# MCU.net
KiCad netlist of a schematic drawn in Altium Designer
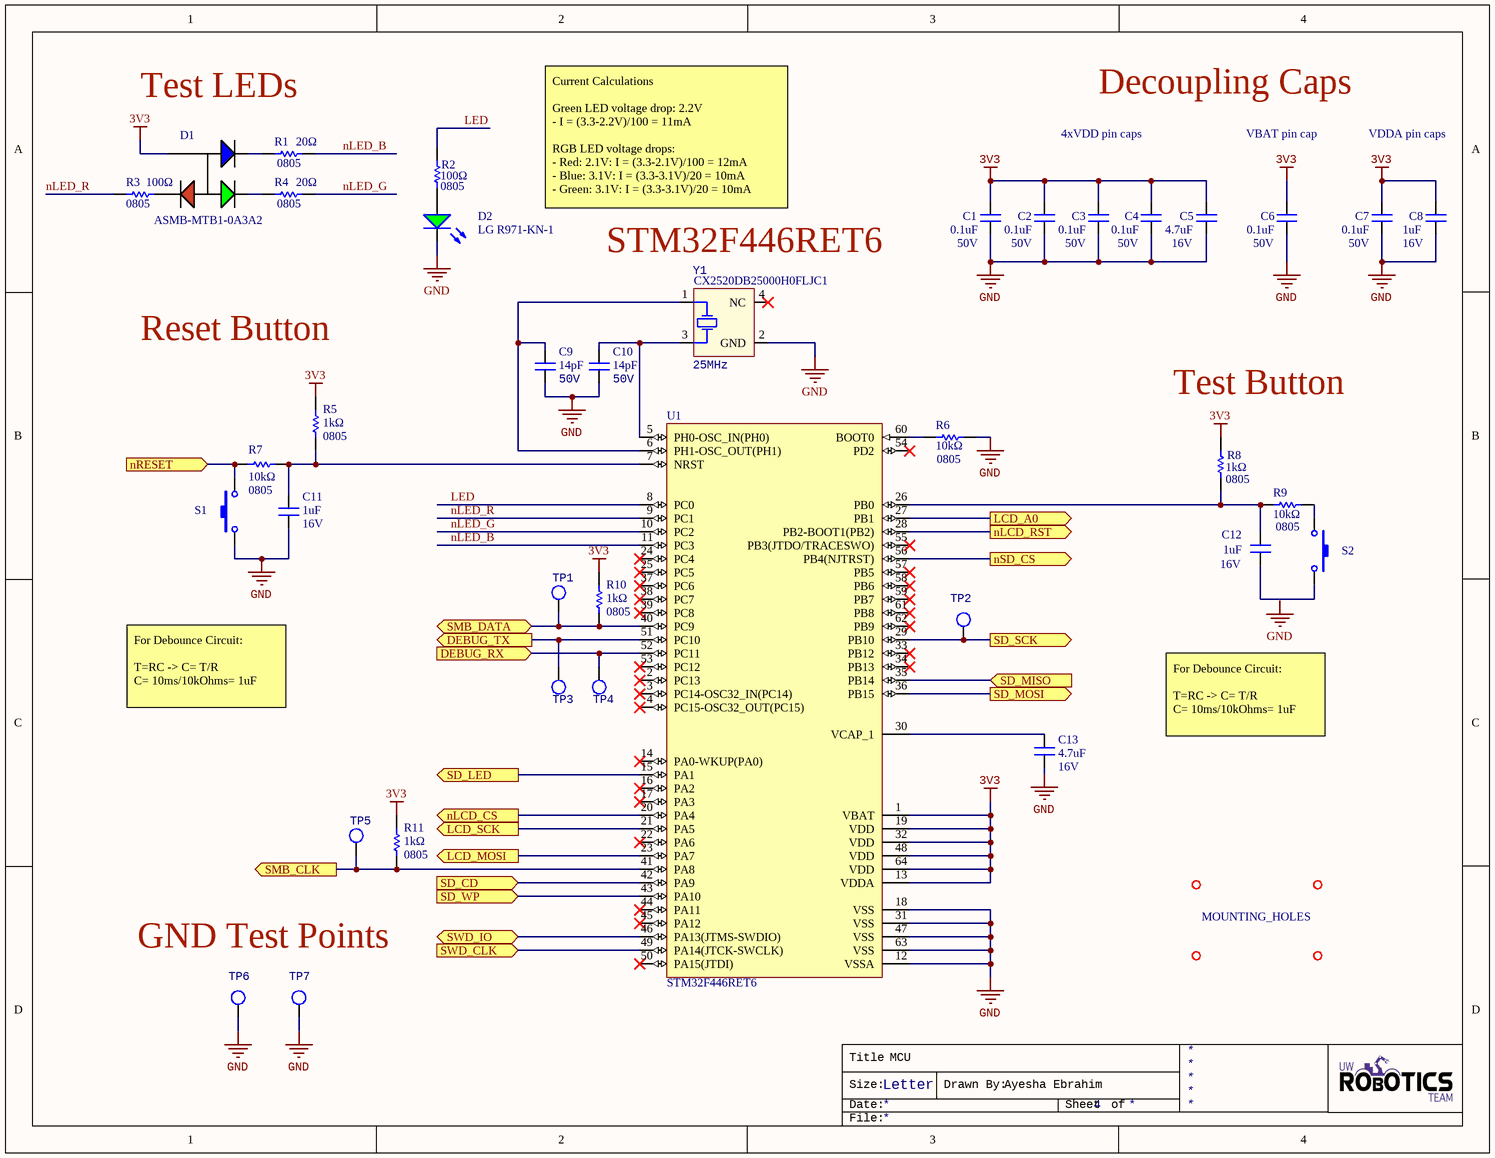
[diagram p0: MCU.SchDoc]

(export (version "E")
  (design (tool "Eeschema 10.0.6"))
  (components
    (comp (ref "C1")
      (value "0.1uF")
      (footprint "CAPC2012X140N")
      (description "CAP CER 0.1UF 50V X7R 0805")
      (fields
        (field (name "TOLERANCE") "10%")
        (field (name "VOLTAGE RATING") "50V")
        (field (name "Comment") "CAP_0.1uF_50V_0805")
      )
      (libsource (lib "UWRT_Schematic_Library_2020") (part "CAP_0.1uF_50V_0805"))
    )
    (comp (ref "C2")
      (value "0.1uF")
      (footprint "CAPC2012X140N")
      (description "CAP CER 0.1UF 50V X7R 0805")
      (fields
        (field (name "TOLERANCE") "10%")
        (field (name "VOLTAGE RATING") "50V")
        (field (name "Comment") "CAP_0.1uF_50V_0805")
      )
      (libsource (lib "UWRT_Schematic_Library_2020") (part "CAP_0.1uF_50V_0805"))
    )
    (comp (ref "C3")
      (value "0.1uF")
      (footprint "CAPC2012X140N")
      (description "CAP CER 0.1UF 50V X7R 0805")
      (fields
        (field (name "TOLERANCE") "10%")
        (field (name "VOLTAGE RATING") "50V")
        (field (name "Comment") "CAP_0.1uF_50V_0805")
      )
      (libsource (lib "UWRT_Schematic_Library_2020") (part "CAP_0.1uF_50V_0805"))
    )
    (comp (ref "C4")
      (value "0.1uF")
      (footprint "CAPC2012X140N")
      (description "CAP CER 0.1UF 50V X7R 0805")
      (fields
        (field (name "TOLERANCE") "10%")
        (field (name "VOLTAGE RATING") "50V")
        (field (name "Comment") "CAP_0.1uF_50V_0805")
      )
      (libsource (lib "UWRT_Schematic_Library_2020") (part "CAP_0.1uF_50V_0805"))
    )
    (comp (ref "C5")
      (value "4.7uF")
      (footprint "CAPC2012X140N")
      (description "CAP CER 4.7UF 16V X5R 0805")
      (fields
        (field (name "TOLERANCE") "10%")
        (field (name "VOLTAGE RATING") "16V")
        (field (name "Comment") "CAP_4.7uF_16V_0805")
      )
      (libsource (lib "UWRT_Schematic_Library_2020") (part "CAP_4.7uF_16V_0805"))
    )
    (comp (ref "C6")
      (value "0.1uF")
      (footprint "CAPC2012X140N")
      (description "CAP CER 0.1UF 50V X7R 0805")
      (fields
        (field (name "TOLERANCE") "10%")
        (field (name "VOLTAGE RATING") "50V")
        (field (name "Comment") "CAP_0.1uF_50V_0805")
      )
      (libsource (lib "UWRT_Schematic_Library_2020") (part "CAP_0.1uF_50V_0805"))
    )
    (comp (ref "C7")
      (value "0.1uF")
      (footprint "CAPC2012X140N")
      (description "CAP CER 0.1UF 50V X7R 0805")
      (fields
        (field (name "TOLERANCE") "10%")
        (field (name "VOLTAGE RATING") "50V")
        (field (name "Comment") "CAP_0.1uF_50V_0805")
      )
      (libsource (lib "UWRT_Schematic_Library_2020") (part "CAP_0.1uF_50V_0805"))
    )
    (comp (ref "C8")
      (value "1uF")
      (footprint "CAPC2012X140N")
      (description "CAP CER 1UF 16V X7R 0805")
      (fields
        (field (name "TOLERANCE") "10%")
        (field (name "VOLTAGE RATING") "16V")
        (field (name "Comment") "CAP_1uF_16V_0805")
      )
      (libsource (lib "UWRT_Schematic_Library_2020") (part "CAP_1uF_16V_0805"))
    )
    (comp (ref "C9")
      (value "14pF")
      (footprint "CAPC0603(1608)55_N")
      (description "Cap Ceramic 14pF 50V C0G 5% SMD 0603 125C Cardboard T/R")
      (fields
        (field (name "TOLERANCE") "5%")
        (field (name "VOLTAGE RATING (DC)") "50V")
        (field (name "Comment") "CL10C140JB8NNNC")
      )
      (libsource (lib "UWRT_Schematic_Library_2020") (part "CL10C140JB8NNNC"))
    )
    (comp (ref "C10")
      (value "14pF")
      (footprint "CAPC0603(1608)55_N")
      (description "Cap Ceramic 14pF 50V C0G 5% SMD 0603 125C Cardboard T/R")
      (fields
        (field (name "TOLERANCE") "5%")
        (field (name "VOLTAGE RATING (DC)") "50V")
        (field (name "Comment") "CL10C140JB8NNNC")
      )
      (libsource (lib "UWRT_Schematic_Library_2020") (part "CL10C140JB8NNNC"))
    )
    (comp (ref "C11")
      (value "1uF")
      (footprint "CAPC2012X140N")
      (description "CAP CER 1UF 16V X7R 0805")
      (fields
        (field (name "TOLERANCE") "10%")
        (field (name "VOLTAGE RATING") "16V")
        (field (name "Comment") "CAP_1uF_16V_0805")
      )
      (libsource (lib "UWRT_Schematic_Library_2020") (part "CAP_1uF_16V_0805"))
    )
    (comp (ref "C12")
      (value "1uF")
      (footprint "CAPC2012X140N")
      (description "CAP CER 1UF 16V X7R 0805")
      (fields
        (field (name "TOLERANCE") "10%")
        (field (name "VOLTAGE RATING") "16V")
        (field (name "Comment") "CAP_1uF_16V_0805")
      )
      (libsource (lib "UWRT_Schematic_Library_2020") (part "CAP_1uF_16V_0805"))
    )
    (comp (ref "C13")
      (value "4.7uF")
      (footprint "CAPC2012X140N")
      (description "CAP CER 4.7UF 16V X5R 0805")
      (fields
        (field (name "TOLERANCE") "10%")
        (field (name "VOLTAGE RATING") "16V")
        (field (name "Comment") "CAP_4.7uF_16V_0805")
      )
      (libsource (lib "UWRT_Schematic_Library_2020") (part "CAP_4.7uF_16V_0805"))
    )
    (comp (ref "D1")
      (value "LED_RGB")
      (footprint "LED_RGB")
      (description "LED RGB DIFFUSED 4PLCC SMD")
      (fields (field (name "MANUFACTURER PART NUMBER 1") "ASMB-MTB1-0A3A2"))
      (libsource (lib "UWRT_Schematic_Library_2020") (part "LED_RGB"))
    )
    (comp (ref "D2")
      (value "DIO_LED_G")
      (footprint "LED_0805_LINE")
      (description "LED GREEN DIFFUSED 0805 SMD")
      (fields (field (name "MANUFACTURER PART NUMBER 1") "LG R971-KN-1"))
      (libsource (lib "UWRT_Schematic_Library_2020") (part "DIO_LED_G"))
    )
    (comp (ref "MH1")
      (value "MOUNTING_HOLES")
      (footprint "MOUNTING_HOLE")
      (description "6cm x 6cm")
      (libsource (lib "UWRT_Schematic_Library_2020") (part "MOUNTING_HOLES"))
    )
    (comp (ref "MH2")
      (value "MOUNTING_HOLES")
      (footprint "MOUNTING_HOLE")
      (description "6cm x 6cm")
      (libsource (lib "UWRT_Schematic_Library_2020") (part "MOUNTING_HOLES"))
    )
    (comp (ref "MH3")
      (value "MOUNTING_HOLES")
      (footprint "MOUNTING_HOLE")
      (description "6cm x 6cm")
      (libsource (lib "UWRT_Schematic_Library_2020") (part "MOUNTING_HOLES"))
    )
    (comp (ref "MH4")
      (value "MOUNTING_HOLES")
      (footprint "MOUNTING_HOLE")
      (description "6cm x 6cm")
      (libsource (lib "UWRT_Schematic_Library_2020") (part "MOUNTING_HOLES"))
    )
    (comp (ref "R1")
      (value "20Ω")
      (footprint "RESC2012X60N")
      (description "RES SMD 20 OHM 1% 1/8W 0805")
      (fields
        (field (name "CASE CODE (IMPERIAL)") "0805")
        (field (name "TOLERANCE") "1%")
        (field (name "Comment") "RES_20Ω_0805")
      )
      (libsource (lib "UWRT_Schematic_Library_2020") (part "RES_20Ω_0805"))
    )
    (comp (ref "R2")
      (value "100Ω")
      (footprint "RESC2012X60N")
      (description "RES SMD 100 OHM 1% 1/8W 0805")
      (fields (field (name "CASE CODE (IMPERIAL)") "0805") (field (name "Comment") "RES_100Ω_0805"))
      (libsource (lib "UWRT_Schematic_Library_2020") (part "RES_100Ω_0805"))
    )
    (comp (ref "R3")
      (value "100Ω")
      (footprint "RESC2012X60N")
      (description "RES SMD 100 OHM 1% 1/8W 0805")
      (fields (field (name "CASE CODE (IMPERIAL)") "0805") (field (name "Comment") "RES_100Ω_0805"))
      (libsource (lib "UWRT_Schematic_Library_2020") (part "RES_100Ω_0805"))
    )
    (comp (ref "R4")
      (value "20Ω")
      (footprint "RESC2012X60N")
      (description "RES SMD 20 OHM 1% 1/8W 0805")
      (fields
        (field (name "CASE CODE (IMPERIAL)") "0805")
        (field (name "TOLERANCE") "1%")
        (field (name "Comment") "RES_20Ω_0805")
      )
      (libsource (lib "UWRT_Schematic_Library_2020") (part "RES_20Ω_0805"))
    )
    (comp (ref "R5")
      (value "1kΩ")
      (footprint "RESC2012X60N")
      (description "RES SMD 1K OHM 1% 1/8W 0805")
      (fields
        (field (name "CASE CODE (IMPERIAL)") "0805")
        (field (name "TOLERANCE") "1%")
        (field (name "Comment") "RES_1kΩ_0805")
      )
      (libsource (lib "UWRT_Schematic_Library_2020") (part "RES_1kΩ_0805"))
    )
    (comp (ref "R6")
      (value "10kΩ")
      (footprint "RESC2012X60N")
      (description "RES SMD 10K OHM 1% 1/8W 0805")
      (fields
        (field (name "CASE CODE (IMPERIAL)") "0805")
        (field (name "TOLERANCE") "1%")
        (field (name "Comment") "RES_10kΩ_0805")
      )
      (libsource (lib "UWRT_Schematic_Library_2020") (part "RES_10kΩ_0805"))
    )
    (comp (ref "R7")
      (value "10kΩ")
      (footprint "RESC2012X60N")
      (description "RES SMD 10K OHM 1% 1/8W 0805")
      (fields
        (field (name "CASE CODE (IMPERIAL)") "0805")
        (field (name "TOLERANCE") "1%")
        (field (name "Comment") "RES_10kΩ_0805")
      )
      (libsource (lib "UWRT_Schematic_Library_2020") (part "RES_10kΩ_0805"))
    )
    (comp (ref "R8")
      (value "1kΩ")
      (footprint "RESC2012X60N")
      (description "RES SMD 1K OHM 1% 1/8W 0805")
      (fields
        (field (name "CASE CODE (IMPERIAL)") "0805")
        (field (name "TOLERANCE") "1%")
        (field (name "Comment") "RES_1kΩ_0805")
      )
      (libsource (lib "UWRT_Schematic_Library_2020") (part "RES_1kΩ_0805"))
    )
    (comp (ref "R9")
      (value "10kΩ")
      (footprint "RESC2012X60N")
      (description "RES SMD 10K OHM 1% 1/8W 0805")
      (fields
        (field (name "CASE CODE (IMPERIAL)") "0805")
        (field (name "TOLERANCE") "1%")
        (field (name "Comment") "RES_10kΩ_0805")
      )
      (libsource (lib "UWRT_Schematic_Library_2020") (part "RES_10kΩ_0805"))
    )
    (comp (ref "R10")
      (value "1kΩ")
      (footprint "RESC2012X60N")
      (description "RES SMD 1K OHM 1% 1/8W 0805")
      (fields
        (field (name "CASE CODE (IMPERIAL)") "0805")
        (field (name "TOLERANCE") "1%")
        (field (name "Comment") "RES_1kΩ_0805")
      )
      (libsource (lib "UWRT_Schematic_Library_2020") (part "RES_1kΩ_0805"))
    )
    (comp (ref "R11")
      (value "1kΩ")
      (footprint "RESC2012X60N")
      (description "RES SMD 1K OHM 1% 1/8W 0805")
      (fields
        (field (name "CASE CODE (IMPERIAL)") "0805")
        (field (name "TOLERANCE") "1%")
        (field (name "Comment") "RES_1kΩ_0805")
      )
      (libsource (lib "UWRT_Schematic_Library_2020") (part "RES_1kΩ_0805"))
    )
    (comp (ref "S1")
      (value "SW_TACTILE")
      (footprint "B3U-1000P")
      (description "Tactile Switch (Grey)")
      (libsource (lib "UWRT_Schematic_Library_2020") (part "SW_TACTILE"))
    )
    (comp (ref "S2")
      (value "SW_TACTILE")
      (footprint "B3U-1000P")
      (description "Tactile Switch (Grey)")
      (libsource (lib "UWRT_Schematic_Library_2020") (part "SW_TACTILE"))
    )
    (comp (ref "TP1")
      (value "TESTPOINT_LOOP")
      (footprint "TESTPOINT_LOOP")
      (description "Loop testpoint through-hole pad")
      (libsource (lib "UWRT_Schematic_Library_2020") (part "TESTPOINT_LOOP"))
    )
    (comp (ref "TP2")
      (value "TESTPOINT_LOOP")
      (footprint "TESTPOINT_LOOP")
      (description "Loop testpoint through-hole pad")
      (libsource (lib "UWRT_Schematic_Library_2020") (part "TESTPOINT_LOOP"))
    )
    (comp (ref "TP3")
      (value "TESTPOINT_LOOP")
      (footprint "TESTPOINT_LOOP")
      (description "Loop testpoint through-hole pad")
      (libsource (lib "UWRT_Schematic_Library_2020") (part "TESTPOINT_LOOP"))
    )
    (comp (ref "TP4")
      (value "TESTPOINT_LOOP")
      (footprint "TESTPOINT_LOOP")
      (description "Loop testpoint through-hole pad")
      (libsource (lib "UWRT_Schematic_Library_2020") (part "TESTPOINT_LOOP"))
    )
    (comp (ref "TP5")
      (value "TESTPOINT_LOOP")
      (footprint "TESTPOINT_LOOP")
      (description "Loop testpoint through-hole pad")
      (libsource (lib "UWRT_Schematic_Library_2020") (part "TESTPOINT_LOOP"))
    )
    (comp (ref "TP6")
      (value "TESTPOINT_LOOP")
      (footprint "TESTPOINT_LOOP")
      (description "Loop testpoint through-hole pad")
      (libsource (lib "UWRT_Schematic_Library_2020") (part "TESTPOINT_LOOP"))
    )
    (comp (ref "TP7")
      (value "TESTPOINT_LOOP")
      (footprint "TESTPOINT_LOOP")
      (description "Loop testpoint through-hole pad")
      (libsource (lib "UWRT_Schematic_Library_2020") (part "TESTPOINT_LOOP"))
    )
    (comp (ref "U1")
      (value "STM32F446RET6")
      (footprint "STM-LQFP64_L")
      (libsource (lib "UWRT_Schematic_Library_2020") (part "MCU_STM32F446RET6"))
    )
    (comp (ref "Y1")
      (value "CRYSTAL_25MHZ")
      (footprint "SOIC254P1016X440-4N")
      (description "CRYSTAL 25.0000MHZ 12PF SMD")
      (fields
        (field (name "MANUFACTURER PART NUMBER 1") "CX2520DB25000H0FLJC1")
        (field (name "FREQUENCY") "25MHz")
      )
      (libsource (lib "UWRT_Schematic_Library_2020") (part "CRYSTAL_25MHZ"))
    )
  )
  (nets
    (net (code "1") (name "/DEBUG_RX") (class "Default")
      (node (ref "TP4") (pin "1") (pintype "passive"))
      (node (ref "U1") (pin "52") (pinfunction "PC11_52") (pintype "bidirectional"))
    )
    (net (code "2") (name "/DEBUG_TX") (class "Default")
      (node (ref "TP3") (pin "1") (pintype "passive"))
      (node (ref "U1") (pin "51") (pinfunction "PC10_51") (pintype "bidirectional"))
    )
    (net (code "3") (name "/LCD_A0") (class "Default")
      (node (ref "U1") (pin "27") (pinfunction "PB1_27") (pintype "bidirectional"))
    )
    (net (code "4") (name "/LCD_MOSI") (class "Default")
      (node (ref "U1") (pin "23") (pinfunction "PA7_23") (pintype "bidirectional"))
    )
    (net (code "5") (name "/LCD_SCK") (class "Default")
      (node (ref "U1") (pin "21") (pinfunction "PA5_21") (pintype "bidirectional"))
    )
    (net (code "6") (name "/LED") (class "Default")
      (node (ref "R2") (pin "2") (pinfunction "2_2") (pintype "passive"))
      (node (ref "U1") (pin "8") (pinfunction "PC0_8") (pintype "bidirectional"))
    )
    (net (code "7") (name "/SD_CD") (class "Default")
      (node (ref "U1") (pin "42") (pinfunction "PA9_42") (pintype "bidirectional"))
    )
    (net (code "8") (name "/SD_LED") (class "Default")
      (node (ref "U1") (pin "15") (pinfunction "PA1_15") (pintype "bidirectional"))
    )
    (net (code "9") (name "/SD_MISO") (class "Default")
      (node (ref "U1") (pin "35") (pinfunction "PB14_35") (pintype "bidirectional"))
    )
    (net (code "10") (name "/SD_MOSI") (class "Default")
      (node (ref "U1") (pin "36") (pinfunction "PB15_36") (pintype "bidirectional"))
    )
    (net (code "11") (name "/SD_SCK") (class "Default")
      (node (ref "TP2") (pin "1") (pintype "passive"))
      (node (ref "U1") (pin "29") (pinfunction "PB10_29") (pintype "bidirectional"))
    )
    (net (code "12") (name "/SD_WP") (class "Default")
      (node (ref "U1") (pin "43") (pinfunction "PA10_43") (pintype "bidirectional"))
    )
    (net (code "13") (name "/SMB_CLK") (class "Default")
      (node (ref "R11") (pin "1") (pinfunction "1_1") (pintype "passive"))
      (node (ref "TP5") (pin "1") (pintype "passive"))
      (node (ref "U1") (pin "41") (pinfunction "PA8_41") (pintype "bidirectional"))
    )
    (net (code "14") (name "/SMB_DATA") (class "Default")
      (node (ref "R10") (pin "1") (pinfunction "1_1") (pintype "passive"))
      (node (ref "TP1") (pin "1") (pintype "passive"))
      (node (ref "U1") (pin "40") (pinfunction "PC9_40") (pintype "bidirectional"))
    )
    (net (code "15") (name "/SWD_CLK") (class "Default")
      (node (ref "U1") (pin "49") (pinfunction "PA14(JTCK-SWCLK)_49") (pintype "bidirectional"))
    )
    (net (code "16") (name "/SWD_IO") (class "Default")
      (node (ref "U1") (pin "46") (pinfunction "PA13(JTMS-SWDIO)_46") (pintype "bidirectional"))
    )
    (net (code "17") (name "/nLCD_CS") (class "Default")
      (node (ref "U1") (pin "20") (pinfunction "PA4_20") (pintype "bidirectional"))
    )
    (net (code "18") (name "/nLCD_RST") (class "Default")
      (node (ref "U1") (pin "28") (pinfunction "PB2-BOOT1(PB2)_28") (pintype "bidirectional"))
    )
    (net (code "19") (name "/nLED_B") (class "Default")
      (node (ref "R1") (pin "2") (pinfunction "2_2") (pintype "passive"))
      (node (ref "U1") (pin "11") (pinfunction "PC3_11") (pintype "bidirectional"))
    )
    (net (code "20") (name "/nLED_G") (class "Default")
      (node (ref "R4") (pin "2") (pinfunction "2_2") (pintype "passive"))
      (node (ref "U1") (pin "10") (pinfunction "PC2_10") (pintype "bidirectional"))
    )
    (net (code "21") (name "/nLED_R") (class "Default")
      (node (ref "R3") (pin "1") (pinfunction "1_1") (pintype "passive"))
      (node (ref "U1") (pin "9") (pinfunction "PC1_9") (pintype "bidirectional"))
    )
    (net (code "22") (name "/nRESET") (class "Default")
      (node (ref "R7") (pin "1") (pinfunction "1_1") (pintype "passive"))
      (node (ref "S1") (pin "1") (pinfunction "1_1") (pintype "passive"))
    )
    (net (code "23") (name "/nSD_CS") (class "Default")
      (node (ref "U1") (pin "56") (pinfunction "PB4(NJTRST)_56") (pintype "bidirectional"))
    )
    (net (code "24") (name "3V3") (class "Default")
      (node (ref "C1") (pin "2") (pinfunction "2_2") (pintype "passive"))
      (node (ref "C2") (pin "2") (pinfunction "2_2") (pintype "passive"))
      (node (ref "C3") (pin "2") (pinfunction "2_2") (pintype "passive"))
      (node (ref "C4") (pin "2") (pinfunction "2_2") (pintype "passive"))
      (node (ref "C5") (pin "2") (pinfunction "2_2") (pintype "passive"))
      (node (ref "C6") (pin "2") (pinfunction "2_2") (pintype "passive"))
      (node (ref "C7") (pin "2") (pinfunction "2_2") (pintype "passive"))
      (node (ref "C8") (pin "2") (pinfunction "2_2") (pintype "passive"))
      (node (ref "D1") (pin "4") (pinfunction "9_4") (pintype "passive"))
      (node (ref "R10") (pin "2") (pinfunction "2_2") (pintype "passive"))
      (node (ref "R11") (pin "2") (pinfunction "2_2") (pintype "passive"))
      (node (ref "R5") (pin "2") (pinfunction "2_2") (pintype "passive"))
      (node (ref "R8") (pin "2") (pinfunction "2_2") (pintype "passive"))
      (node (ref "U1") (pin "1") (pinfunction "VBAT_1") (pintype "power_in"))
      (node (ref "U1") (pin "13") (pinfunction "VDDA_13") (pintype "power_in"))
      (node (ref "U1") (pin "19") (pinfunction "VDD_19") (pintype "power_in"))
      (node (ref "U1") (pin "32") (pinfunction "VDD_32") (pintype "power_in"))
      (node (ref "U1") (pin "48") (pinfunction "VDD_48") (pintype "power_in"))
      (node (ref "U1") (pin "64") (pinfunction "VDD_64") (pintype "power_in"))
    )
    (net (code "25") (name "GND") (class "Default")
      (node (ref "C1") (pin "1") (pinfunction "1_1") (pintype "passive"))
      (node (ref "C10") (pin "1") (pinfunction "1_1") (pintype "passive"))
      (node (ref "C11") (pin "1") (pinfunction "1_1") (pintype "passive"))
      (node (ref "C13") (pin "1") (pinfunction "1_1") (pintype "passive"))
      (node (ref "C2") (pin "1") (pinfunction "1_1") (pintype "passive"))
      (node (ref "C3") (pin "1") (pinfunction "1_1") (pintype "passive"))
      (node (ref "C4") (pin "1") (pinfunction "1_1") (pintype "passive"))
      (node (ref "C5") (pin "1") (pinfunction "1_1") (pintype "passive"))
      (node (ref "C6") (pin "1") (pinfunction "1_1") (pintype "passive"))
      (node (ref "C7") (pin "1") (pinfunction "1_1") (pintype "passive"))
      (node (ref "C8") (pin "1") (pinfunction "1_1") (pintype "passive"))
      (node (ref "C9") (pin "1") (pinfunction "1_1") (pintype "passive"))
      (node (ref "D2") (pin "2") (pinfunction "K_2") (pintype "passive"))
      (node (ref "R6") (pin "2") (pinfunction "2_2") (pintype "passive"))
      (node (ref "S1") (pin "2") (pinfunction "2_2") (pintype "passive"))
      (node (ref "TP6") (pin "1") (pintype "passive"))
      (node (ref "TP7") (pin "1") (pintype "passive"))
      (node (ref "U1") (pin "12") (pinfunction "VSSA_12") (pintype "power_in"))
      (node (ref "U1") (pin "18") (pinfunction "VSS_18") (pintype "power_in"))
      (node (ref "U1") (pin "31") (pinfunction "VSS_31") (pintype "power_in"))
      (node (ref "U1") (pin "47") (pinfunction "VSS_47") (pintype "power_in"))
      (node (ref "U1") (pin "63") (pinfunction "VSS_63") (pintype "power_in"))
      (node (ref "Y1") (pin "2") (pinfunction "GND_2") (pintype "power_in"))
    )
    (net (code "26") (name "Net-(C12-Pad1)") (class "Default")
      (node (ref "C12") (pin "1") (pinfunction "1_1") (pintype "passive"))
      (node (ref "S2") (pin "2") (pinfunction "2_2") (pintype "passive"))
    )
    (net (code "27") (name "Net-(D1-10)") (class "Default")
      (node (ref "D1") (pin "3") (pinfunction "10_3") (pintype "passive"))
      (node (ref "R1") (pin "1") (pinfunction "1_1") (pintype "passive"))
    )
    (net (code "28") (name "Net-(D1-11)") (class "Default")
      (node (ref "D1") (pin "1") (pinfunction "11_1") (pintype "passive"))
      (node (ref "R3") (pin "2") (pinfunction "2_2") (pintype "passive"))
    )
    (net (code "29") (name "Net-(D1-12)") (class "Default")
      (node (ref "D1") (pin "2") (pinfunction "12_2") (pintype "passive"))
      (node (ref "R4") (pin "1") (pinfunction "1_1") (pintype "passive"))
    )
    (net (code "30") (name "Net-(D2-A)") (class "Default")
      (node (ref "D2") (pin "1") (pinfunction "A_1") (pintype "passive"))
      (node (ref "R2") (pin "1") (pinfunction "1_1") (pintype "passive"))
    )
    (net (code "31") (name "Net-(R9-Pad2)") (class "Default")
      (node (ref "R9") (pin "2") (pinfunction "2_2") (pintype "passive"))
      (node (ref "S2") (pin "1") (pinfunction "1_1") (pintype "passive"))
    )
    (net (code "32") (name "Net-(U1-BOOT0)") (class "Default")
      (node (ref "R6") (pin "1") (pinfunction "1_1") (pintype "passive"))
      (node (ref "U1") (pin "60") (pinfunction "BOOT0_60") (pintype "input"))
    )
    (net (code "33") (name "Net-(U1-NRST)") (class "Default")
      (node (ref "C11") (pin "2") (pinfunction "2_2") (pintype "passive"))
      (node (ref "R5") (pin "1") (pinfunction "1_1") (pintype "passive"))
      (node (ref "R7") (pin "2") (pinfunction "2_2") (pintype "passive"))
      (node (ref "U1") (pin "7") (pinfunction "NRST_7") (pintype "bidirectional"))
    )
    (net (code "34") (name "Net-(U1-PB0)") (class "Default")
      (node (ref "C12") (pin "2") (pinfunction "2_2") (pintype "passive"))
      (node (ref "R8") (pin "1") (pinfunction "1_1") (pintype "passive"))
      (node (ref "R9") (pin "1") (pinfunction "1_1") (pintype "passive"))
      (node (ref "U1") (pin "26") (pinfunction "PB0_26") (pintype "bidirectional"))
    )
    (net (code "35") (name "Net-(U1-PH0-OSC_IN(PH0))") (class "Default")
      (node (ref "C10") (pin "2") (pinfunction "2_2") (pintype "passive"))
      (node (ref "U1") (pin "5") (pinfunction "PH0-OSC_IN(PH0)_5") (pintype "bidirectional"))
      (node (ref "Y1") (pin "3") (pinfunction "HOT_3") (pintype "passive"))
    )
    (net (code "36") (name "Net-(U1-PH1-OSC_OUT(PH1))") (class "Default")
      (node (ref "C9") (pin "2") (pinfunction "2_2") (pintype "passive"))
      (node (ref "U1") (pin "6") (pinfunction "PH1-OSC_OUT(PH1)_6") (pintype "bidirectional"))
      (node (ref "Y1") (pin "1") (pinfunction "HOT_1") (pintype "passive"))
    )
    (net (code "37") (name "Net-(U1-VCAP_1)") (class "Default")
      (node (ref "C13") (pin "2") (pinfunction "2_2") (pintype "passive"))
      (node (ref "U1") (pin "30") (pinfunction "VCAP_1_30") (pintype "passive"))
    )
    (net (code "38") (name "unconnected-(U1-PA0-WKUP(PA0)-Pad14)") (class "Default")
      (node (ref "U1") (pin "14") (pinfunction "PA0-WKUP(PA0)_14") (pintype "bidirectional+no_connect"))
    )
    (net (code "39") (name "unconnected-(U1-PA2-Pad16)") (class "Default")
      (node (ref "U1") (pin "16") (pinfunction "PA2_16") (pintype "bidirectional+no_connect"))
    )
    (net (code "40") (name "unconnected-(U1-PA3-Pad17)") (class "Default")
      (node (ref "U1") (pin "17") (pinfunction "PA3_17") (pintype "bidirectional+no_connect"))
    )
    (net (code "41") (name "unconnected-(U1-PA6-Pad22)") (class "Default")
      (node (ref "U1") (pin "22") (pinfunction "PA6_22") (pintype "bidirectional+no_connect"))
    )
    (net (code "42") (name "unconnected-(U1-PA11-Pad44)") (class "Default")
      (node (ref "U1") (pin "44") (pinfunction "PA11_44") (pintype "bidirectional+no_connect"))
    )
    (net (code "43") (name "unconnected-(U1-PA12-Pad45)") (class "Default")
      (node (ref "U1") (pin "45") (pinfunction "PA12_45") (pintype "bidirectional+no_connect"))
    )
    (net (code "44") (name "unconnected-(U1-PA15(JTDI)-Pad50)") (class "Default")
      (node (ref "U1") (pin "50") (pinfunction "PA15(JTDI)_50") (pintype "bidirectional+no_connect"))
    )
    (net (code "45") (name "unconnected-(U1-PB3(JTDO{slash}TRACESWO)-Pad55)") (class "Default")
      (node (ref "U1") (pin "55") (pinfunction "PB3(JTDO/TRACESWO)_55") (pintype "bidirectional+no_connect"))
    )
    (net (code "46") (name "unconnected-(U1-PB5-Pad57)") (class "Default")
      (node (ref "U1") (pin "57") (pinfunction "PB5_57") (pintype "bidirectional+no_connect"))
    )
    (net (code "47") (name "unconnected-(U1-PB6-Pad58)") (class "Default")
      (node (ref "U1") (pin "58") (pinfunction "PB6_58") (pintype "bidirectional+no_connect"))
    )
    (net (code "48") (name "unconnected-(U1-PB7-Pad59)") (class "Default")
      (node (ref "U1") (pin "59") (pinfunction "PB7_59") (pintype "bidirectional+no_connect"))
    )
    (net (code "49") (name "unconnected-(U1-PB8-Pad61)") (class "Default")
      (node (ref "U1") (pin "61") (pinfunction "PB8_61") (pintype "bidirectional+no_connect"))
    )
    (net (code "50") (name "unconnected-(U1-PB9-Pad62)") (class "Default")
      (node (ref "U1") (pin "62") (pinfunction "PB9_62") (pintype "bidirectional+no_connect"))
    )
    (net (code "51") (name "unconnected-(U1-PB12-Pad33)") (class "Default")
      (node (ref "U1") (pin "33") (pinfunction "PB12_33") (pintype "bidirectional+no_connect"))
    )
    (net (code "52") (name "unconnected-(U1-PB13-Pad34)") (class "Default")
      (node (ref "U1") (pin "34") (pinfunction "PB13_34") (pintype "bidirectional+no_connect"))
    )
    (net (code "53") (name "unconnected-(U1-PC4-Pad24)") (class "Default")
      (node (ref "U1") (pin "24") (pinfunction "PC4_24") (pintype "bidirectional+no_connect"))
    )
    (net (code "54") (name "unconnected-(U1-PC5-Pad25)") (class "Default")
      (node (ref "U1") (pin "25") (pinfunction "PC5_25") (pintype "bidirectional+no_connect"))
    )
    (net (code "55") (name "unconnected-(U1-PC6-Pad37)") (class "Default")
      (node (ref "U1") (pin "37") (pinfunction "PC6_37") (pintype "bidirectional+no_connect"))
    )
    (net (code "56") (name "unconnected-(U1-PC7-Pad38)") (class "Default")
      (node (ref "U1") (pin "38") (pinfunction "PC7_38") (pintype "bidirectional+no_connect"))
    )
    (net (code "57") (name "unconnected-(U1-PC8-Pad39)") (class "Default")
      (node (ref "U1") (pin "39") (pinfunction "PC8_39") (pintype "bidirectional+no_connect"))
    )
    (net (code "58") (name "unconnected-(U1-PC12-Pad53)") (class "Default")
      (node (ref "U1") (pin "53") (pinfunction "PC12_53") (pintype "bidirectional+no_connect"))
    )
    (net (code "59") (name "unconnected-(U1-PC13-Pad2)") (class "Default")
      (node (ref "U1") (pin "2") (pinfunction "PC13_2") (pintype "bidirectional+no_connect"))
    )
    (net (code "60") (name "unconnected-(U1-PC14-OSC32_IN(PC14)-Pad3)") (class "Default")
      (node (ref "U1") (pin "3") (pinfunction "PC14-OSC32_IN(PC14)_3") (pintype "bidirectional+no_connect"))
    )
    (net (code "61") (name "unconnected-(U1-PC15-OSC32_OUT(PC15)-Pad4)") (class "Default")
      (node (ref "U1") (pin "4") (pinfunction "PC15-OSC32_OUT(PC15)_4") (pintype "bidirectional+no_connect"))
    )
    (net (code "62") (name "unconnected-(U1-PD2-Pad54)") (class "Default")
      (node (ref "U1") (pin "54") (pinfunction "PD2_54") (pintype "bidirectional+no_connect"))
    )
    (net (code "63") (name "unconnected-(Y1-NC-Pad4)") (class "Default")
      (node (ref "Y1") (pin "4") (pinfunction "NC_4") (pintype "passive+no_connect"))
    )
  )
)
